# Power_Board_Rev_A.net
KiCad netlist of a schematic drawn in EAGLE
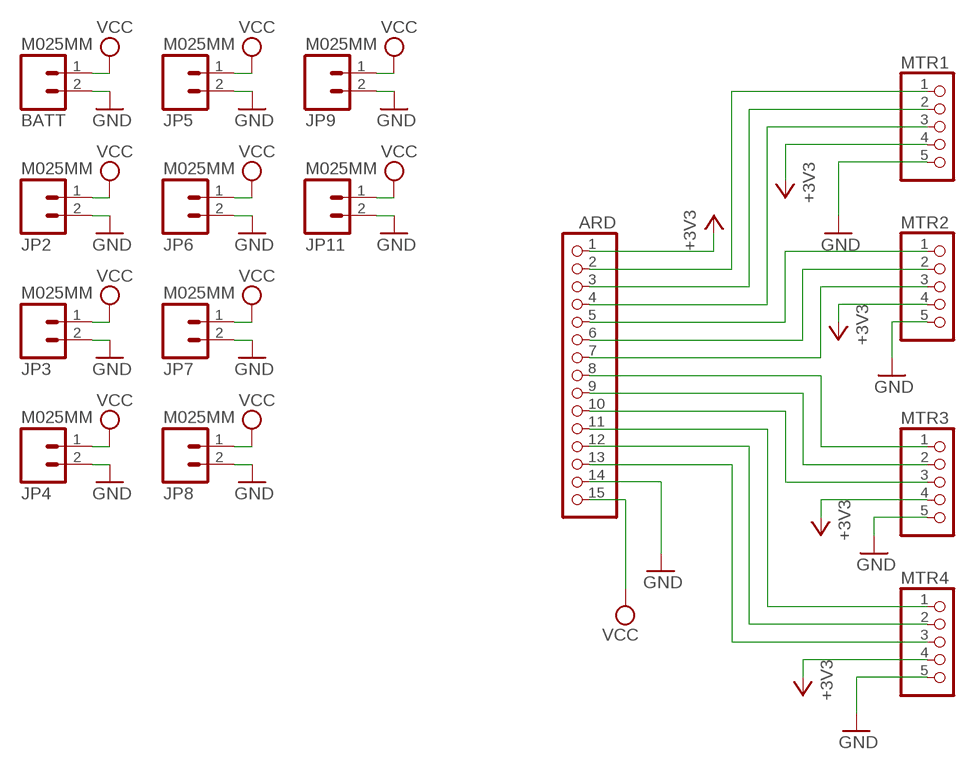
[diagram p0: schematic, sheet 1]

(export (version "E")
  (design (tool "Eeschema 10.0.6"))
  (components
    (comp (ref "ARD")
      (value "PINHD-1X15")
      (footprint "eagle-import:1X15")
      (libsource (lib "eagle-import") (part "PINHD-1X15"))
    )
    (comp (ref "BATT")
      (value "M025MM")
      (footprint "eagle-import:SCREWTERMINAL-5MM-2")
      (libsource (lib "eagle-import") (part "M025MM"))
    )
    (comp (ref "JP2")
      (value "M025MM")
      (footprint "eagle-import:SCREWTERMINAL-5MM-2")
      (libsource (lib "eagle-import") (part "M025MM"))
    )
    (comp (ref "JP3")
      (value "M025MM")
      (footprint "eagle-import:SCREWTERMINAL-5MM-2")
      (libsource (lib "eagle-import") (part "M025MM"))
    )
    (comp (ref "JP4")
      (value "M025MM")
      (footprint "eagle-import:SCREWTERMINAL-5MM-2")
      (libsource (lib "eagle-import") (part "M025MM"))
    )
    (comp (ref "JP5")
      (value "M025MM")
      (footprint "eagle-import:SCREWTERMINAL-5MM-2")
      (libsource (lib "eagle-import") (part "M025MM"))
    )
    (comp (ref "JP6")
      (value "M025MM")
      (footprint "eagle-import:SCREWTERMINAL-5MM-2")
      (libsource (lib "eagle-import") (part "M025MM"))
    )
    (comp (ref "JP7")
      (value "M025MM")
      (footprint "eagle-import:SCREWTERMINAL-5MM-2")
      (libsource (lib "eagle-import") (part "M025MM"))
    )
    (comp (ref "JP8")
      (value "M025MM")
      (footprint "eagle-import:SCREWTERMINAL-5MM-2")
      (libsource (lib "eagle-import") (part "M025MM"))
    )
    (comp (ref "JP9")
      (value "M025MM")
      (footprint "eagle-import:SCREWTERMINAL-5MM-2")
      (libsource (lib "eagle-import") (part "M025MM"))
    )
    (comp (ref "JP11")
      (value "M025MM")
      (footprint "eagle-import:SCREWTERMINAL-5MM-2")
      (libsource (lib "eagle-import") (part "M025MM"))
    )
    (comp (ref "MTR1")
      (value "PINHD-1X5")
      (footprint "eagle-import:1X05")
      (libsource (lib "eagle-import") (part "PINHD-1X5"))
    )
    (comp (ref "MTR2")
      (value "PINHD-1X5")
      (footprint "eagle-import:1X05")
      (libsource (lib "eagle-import") (part "PINHD-1X5"))
    )
    (comp (ref "MTR3")
      (value "PINHD-1X5")
      (footprint "eagle-import:1X05")
      (libsource (lib "eagle-import") (part "PINHD-1X5"))
    )
    (comp (ref "MTR4")
      (value "PINHD-1X5")
      (footprint "eagle-import:1X05")
      (libsource (lib "eagle-import") (part "PINHD-1X5"))
    )
  )
  (nets
    (net (code "1") (name "+3V3") (class "Default")
      (node (ref "ARD") (pin "1") (pinfunction "1_1") (pintype "passive"))
      (node (ref "MTR1") (pin "4") (pinfunction "4_4") (pintype "passive"))
      (node (ref "MTR2") (pin "4") (pinfunction "4_4") (pintype "passive"))
      (node (ref "MTR3") (pin "4") (pinfunction "4_4") (pintype "passive"))
      (node (ref "MTR4") (pin "4") (pinfunction "4_4") (pintype "passive"))
    )
    (net (code "2") (name "GND") (class "Default")
      (node (ref "ARD") (pin "14") (pinfunction "14_14") (pintype "passive"))
      (node (ref "BATT") (pin "2") (pinfunction "2_2") (pintype "passive"))
      (node (ref "JP11") (pin "2") (pinfunction "2_2") (pintype "passive"))
      (node (ref "JP2") (pin "2") (pinfunction "2_2") (pintype "passive"))
      (node (ref "JP3") (pin "2") (pinfunction "2_2") (pintype "passive"))
      (node (ref "JP4") (pin "2") (pinfunction "2_2") (pintype "passive"))
      (node (ref "JP5") (pin "2") (pinfunction "2_2") (pintype "passive"))
      (node (ref "JP6") (pin "2") (pinfunction "2_2") (pintype "passive"))
      (node (ref "JP7") (pin "2") (pinfunction "2_2") (pintype "passive"))
      (node (ref "JP8") (pin "2") (pinfunction "2_2") (pintype "passive"))
      (node (ref "JP9") (pin "2") (pinfunction "2_2") (pintype "passive"))
      (node (ref "MTR1") (pin "5") (pinfunction "5_5") (pintype "passive"))
      (node (ref "MTR2") (pin "5") (pinfunction "5_5") (pintype "passive"))
      (node (ref "MTR3") (pin "5") (pinfunction "5_5") (pintype "passive"))
      (node (ref "MTR4") (pin "5") (pinfunction "5_5") (pintype "passive"))
    )
    (net (code "3") (name "Net-(ARD-Pad2)") (class "Default")
      (node (ref "ARD") (pin "2") (pinfunction "2_2") (pintype "passive"))
      (node (ref "MTR1") (pin "1") (pinfunction "1_1") (pintype "passive"))
    )
    (net (code "4") (name "Net-(ARD-Pad3)") (class "Default")
      (node (ref "ARD") (pin "3") (pinfunction "3_3") (pintype "passive"))
      (node (ref "MTR1") (pin "2") (pinfunction "2_2") (pintype "passive"))
    )
    (net (code "5") (name "Net-(ARD-Pad4)") (class "Default")
      (node (ref "ARD") (pin "4") (pinfunction "4_4") (pintype "passive"))
      (node (ref "MTR1") (pin "3") (pinfunction "3_3") (pintype "passive"))
    )
    (net (code "6") (name "Net-(ARD-Pad5)") (class "Default")
      (node (ref "ARD") (pin "5") (pinfunction "5_5") (pintype "passive"))
      (node (ref "MTR2") (pin "1") (pinfunction "1_1") (pintype "passive"))
    )
    (net (code "7") (name "Net-(ARD-Pad6)") (class "Default")
      (node (ref "ARD") (pin "6") (pinfunction "6_6") (pintype "passive"))
      (node (ref "MTR2") (pin "2") (pinfunction "2_2") (pintype "passive"))
    )
    (net (code "8") (name "Net-(ARD-Pad7)") (class "Default")
      (node (ref "ARD") (pin "7") (pinfunction "7_7") (pintype "passive"))
      (node (ref "MTR2") (pin "3") (pinfunction "3_3") (pintype "passive"))
    )
    (net (code "9") (name "Net-(ARD-Pad8)") (class "Default")
      (node (ref "ARD") (pin "8") (pinfunction "8_8") (pintype "passive"))
      (node (ref "MTR3") (pin "1") (pinfunction "1_1") (pintype "passive"))
    )
    (net (code "10") (name "Net-(ARD-Pad9)") (class "Default")
      (node (ref "ARD") (pin "9") (pinfunction "9_9") (pintype "passive"))
      (node (ref "MTR3") (pin "2") (pinfunction "2_2") (pintype "passive"))
    )
    (net (code "11") (name "Net-(ARD-Pad10)") (class "Default")
      (node (ref "ARD") (pin "10") (pinfunction "10_10") (pintype "passive"))
      (node (ref "MTR3") (pin "3") (pinfunction "3_3") (pintype "passive"))
    )
    (net (code "12") (name "Net-(ARD-Pad11)") (class "Default")
      (node (ref "ARD") (pin "11") (pinfunction "11_11") (pintype "passive"))
      (node (ref "MTR4") (pin "1") (pinfunction "1_1") (pintype "passive"))
    )
    (net (code "13") (name "Net-(ARD-Pad12)") (class "Default")
      (node (ref "ARD") (pin "12") (pinfunction "12_12") (pintype "passive"))
      (node (ref "MTR4") (pin "2") (pinfunction "2_2") (pintype "passive"))
    )
    (net (code "14") (name "Net-(ARD-Pad13)") (class "Default")
      (node (ref "ARD") (pin "13") (pinfunction "13_13") (pintype "passive"))
      (node (ref "MTR4") (pin "3") (pinfunction "3_3") (pintype "passive"))
    )
    (net (code "15") (name "VCC") (class "Default")
      (node (ref "ARD") (pin "15") (pinfunction "15_15") (pintype "passive"))
      (node (ref "BATT") (pin "1") (pinfunction "1_1") (pintype "passive"))
      (node (ref "JP11") (pin "1") (pinfunction "1_1") (pintype "passive"))
      (node (ref "JP2") (pin "1") (pinfunction "1_1") (pintype "passive"))
      (node (ref "JP3") (pin "1") (pinfunction "1_1") (pintype "passive"))
      (node (ref "JP4") (pin "1") (pinfunction "1_1") (pintype "passive"))
      (node (ref "JP5") (pin "1") (pinfunction "1_1") (pintype "passive"))
      (node (ref "JP6") (pin "1") (pinfunction "1_1") (pintype "passive"))
      (node (ref "JP7") (pin "1") (pinfunction "1_1") (pintype "passive"))
      (node (ref "JP8") (pin "1") (pinfunction "1_1") (pintype "passive"))
      (node (ref "JP9") (pin "1") (pinfunction "1_1") (pintype "passive"))
    )
  )
)
